# Sheet_1_2025-12-18.net
KiCad netlist of a schematic drawn in Altium Designer
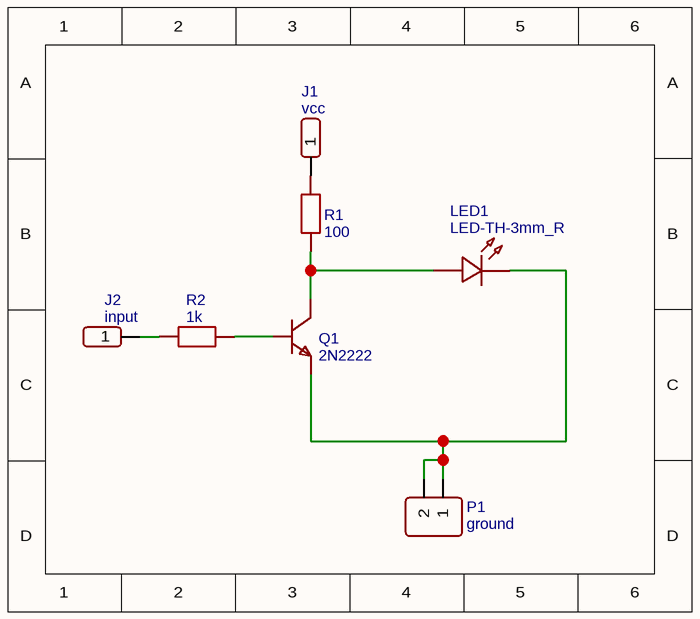
[diagram p0: Sheet_1_2025-12-18.schdoc]

(export (version "E")
  (design (tool "Eeschema 10.0.6"))
  (components
    (comp (ref "J1")
      (value "vcc")
      (fields (field (name "CONTRIBUTOR") "LCEDA_Lib"))
      (libsource (lib "altium-import") (part "root_1_vcc_"))
    )
    (comp (ref "J2")
      (value "input")
      (fields (field (name "CONTRIBUTOR") "LCEDA_Lib"))
      (libsource (lib "altium-import") (part "root_2_input_"))
    )
    (comp (ref "LED1")
      (value "LED-TH-3mm_R")
      (fields
        (field (name "MANUFACTURER") "EVERLIGHT(台湾亿光)")
        (field (name "MANUFACTURER PART") "204-10SDRD/S530-A3-L")
        (field (name "CONTRIBUTOR") "LCEDA_Lib")
      )
      (libsource (lib "altium-import") (part "root_0_LED-TH-3mm_R_"))
    )
    (comp (ref "P1")
      (value "ground")
      (fields (field (name "CONTRIBUTOR") "LCEDA_Lib"))
      (libsource (lib "altium-import") (part "root_3_ground_"))
    )
    (comp (ref "Q1")
      (value "2N2222")
      (fields
        (field (name "MANUFACTURER") "ST(先科)")
        (field (name "MANUFACTURER PART") "2N2222A")
        (field (name "CONTRIBUTOR") "LCSC")
      )
      (libsource (lib "altium-import") (part "root_0_2N2222_"))
    )
    (comp (ref "R1")
      (value "100")
      (fields (field (name "CONTRIBUTOR") "LCEDA_Lib"))
      (libsource (lib "altium-import") (part "root_1_100_"))
    )
    (comp (ref "R2")
      (value "1k")
      (fields (field (name "CONTRIBUTOR") "LCEDA_Lib"))
      (libsource (lib "altium-import") (part "root_2_1k_"))
    )
  )
  (nets
    (net (code "1") (name "Net-(J1-Pad1)") (class "Default")
      (node (ref "J1") (pin "1") (pinfunction "1_1") (pintype "passive"))
      (node (ref "R1") (pin "2") (pinfunction "2_2") (pintype "passive"))
    )
    (net (code "2") (name "Net-(J2-Pad1)") (class "Default")
      (node (ref "J2") (pin "1") (pinfunction "1_1") (pintype "passive"))
      (node (ref "R2") (pin "2") (pinfunction "2_2") (pintype "passive"))
    )
    (net (code "3") (name "Net-(Q1-B)") (class "Default")
      (node (ref "Q1") (pin "2") (pinfunction "B_2") (pintype "passive"))
      (node (ref "R2") (pin "1") (pinfunction "1_1") (pintype "passive"))
    )
    (net (code "4") (name "Net-(Q1-C)") (class "Default")
      (node (ref "LED1") (pin "1") (pinfunction "1_1") (pintype "passive"))
      (node (ref "Q1") (pin "3") (pinfunction "C_3") (pintype "passive"))
      (node (ref "R1") (pin "1") (pinfunction "1_1") (pintype "passive"))
    )
    (net (code "5") (name "Net-(Q1-E)") (class "Default")
      (node (ref "LED1") (pin "2") (pinfunction "2_2") (pintype "passive"))
      (node (ref "P1") (pin "1") (pinfunction "1_1") (pintype "passive"))
      (node (ref "P1") (pin "2") (pinfunction "2_2") (pintype "passive"))
      (node (ref "Q1") (pin "1") (pinfunction "E_1") (pintype "passive"))
    )
  )
)
